# NOR_GATE.net
KiCad netlist of a schematic drawn in EAGLE
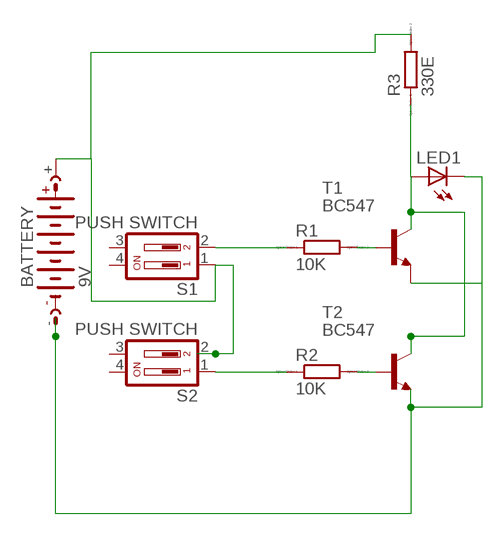
[diagram p0: schematic, sheet 1]

(export (version "E")
  (design (tool "Eeschema 10.0.6"))
  (components
    (comp (ref "BATTERY")
      (value "9V")
      (footprint "eagle-import:AB9V")
      (libsource (lib "eagle-import") (part "AB9V"))
    )
    (comp (ref "LED1")
      (value "LED5MM")
      (footprint "eagle-import:LED5MM")
      (libsource (lib "eagle-import") (part "LED5MM"))
    )
    (comp (ref "R1")
      (value "10K")
      (footprint "eagle-import:0204_7")
      (libsource (lib "eagle-import") (part "R0204/7"))
    )
    (comp (ref "R2")
      (value "10K")
      (footprint "eagle-import:0204_7")
      (libsource (lib "eagle-import") (part "R0204/7"))
    )
    (comp (ref "R3")
      (value "330E")
      (footprint "eagle-import:0204_7")
      (libsource (lib "eagle-import") (part "R0204/7"))
    )
    (comp (ref "S1")
      (value "PUSH SWITCH")
      (footprint "eagle-import:DS-02")
      (libsource (lib "eagle-import") (part "DS02"))
    )
    (comp (ref "S2")
      (value "PUSH SWITCH")
      (footprint "eagle-import:DS-02")
      (libsource (lib "eagle-import") (part "DS02"))
    )
    (comp (ref "T1")
      (value "BC547")
      (footprint "eagle-import:TO92")
      (libsource (lib "eagle-import") (part "BC547"))
    )
    (comp (ref "T2")
      (value "BC547")
      (footprint "eagle-import:TO92")
      (libsource (lib "eagle-import") (part "BC547"))
    )
  )
  (nets
    (net (code "1") (name "Net-(BATTERY-Pad+)") (class "Default")
      (node (ref "BATTERY") (pin "+") (pinfunction "+_+") (pintype "passive"))
      (node (ref "R3") (pin "2") (pinfunction "2_2") (pintype "passive"))
      (node (ref "S1") (pin "1") (pinfunction "1_1") (pintype "passive"))
      (node (ref "S2") (pin "2") (pinfunction "2_2") (pintype "passive"))
    )
    (net (code "2") (name "Net-(LED1-C)") (class "Default")
      (node (ref "BATTERY") (pin "-") (pinfunction "-_-") (pintype "passive"))
      (node (ref "LED1") (pin "K") (pinfunction "C_K") (pintype "passive"))
      (node (ref "T1") (pin "1") (pinfunction "E_1") (pintype "passive"))
      (node (ref "T2") (pin "1") (pinfunction "E_1") (pintype "passive"))
    )
    (net (code "3") (name "Net-(R1-Pad1)") (class "Default")
      (node (ref "R1") (pin "1") (pinfunction "1_1") (pintype "passive"))
      (node (ref "S1") (pin "2") (pinfunction "2_2") (pintype "passive"))
    )
    (net (code "4") (name "Net-(R2-Pad1)") (class "Default")
      (node (ref "R2") (pin "1") (pinfunction "1_1") (pintype "passive"))
      (node (ref "S2") (pin "1") (pinfunction "1_1") (pintype "passive"))
    )
    (net (code "5") (name "Net-(T1-B)") (class "Default")
      (node (ref "R1") (pin "2") (pinfunction "2_2") (pintype "passive"))
      (node (ref "T1") (pin "2") (pinfunction "B_2") (pintype "passive"))
    )
    (net (code "6") (name "Net-(T1-C)") (class "Default")
      (node (ref "LED1") (pin "A") (pinfunction "A_A") (pintype "passive"))
      (node (ref "R3") (pin "1") (pinfunction "1_1") (pintype "passive"))
      (node (ref "T1") (pin "3") (pinfunction "C_3") (pintype "passive"))
      (node (ref "T2") (pin "3") (pinfunction "C_3") (pintype "passive"))
    )
    (net (code "7") (name "Net-(T2-B)") (class "Default")
      (node (ref "R2") (pin "2") (pinfunction "2_2") (pintype "passive"))
      (node (ref "T2") (pin "2") (pinfunction "B_2") (pintype "passive"))
    )
    (net (code "8") (name "unconnected-(S1-Pad3)") (class "Default")
      (node (ref "S1") (pin "3") (pinfunction "3_3") (pintype "passive"))
    )
    (net (code "9") (name "unconnected-(S1-Pad4)") (class "Default")
      (node (ref "S1") (pin "4") (pinfunction "4_4") (pintype "passive"))
    )
    (net (code "10") (name "unconnected-(S2-Pad3)") (class "Default")
      (node (ref "S2") (pin "3") (pinfunction "3_3") (pintype "passive"))
    )
    (net (code "11") (name "unconnected-(S2-Pad4)") (class "Default")
      (node (ref "S2") (pin "4") (pinfunction "4_4") (pintype "passive"))
    )
  )
)
